# USB2_Replication.net
KiCad netlist of a schematic drawn in Altium Designer
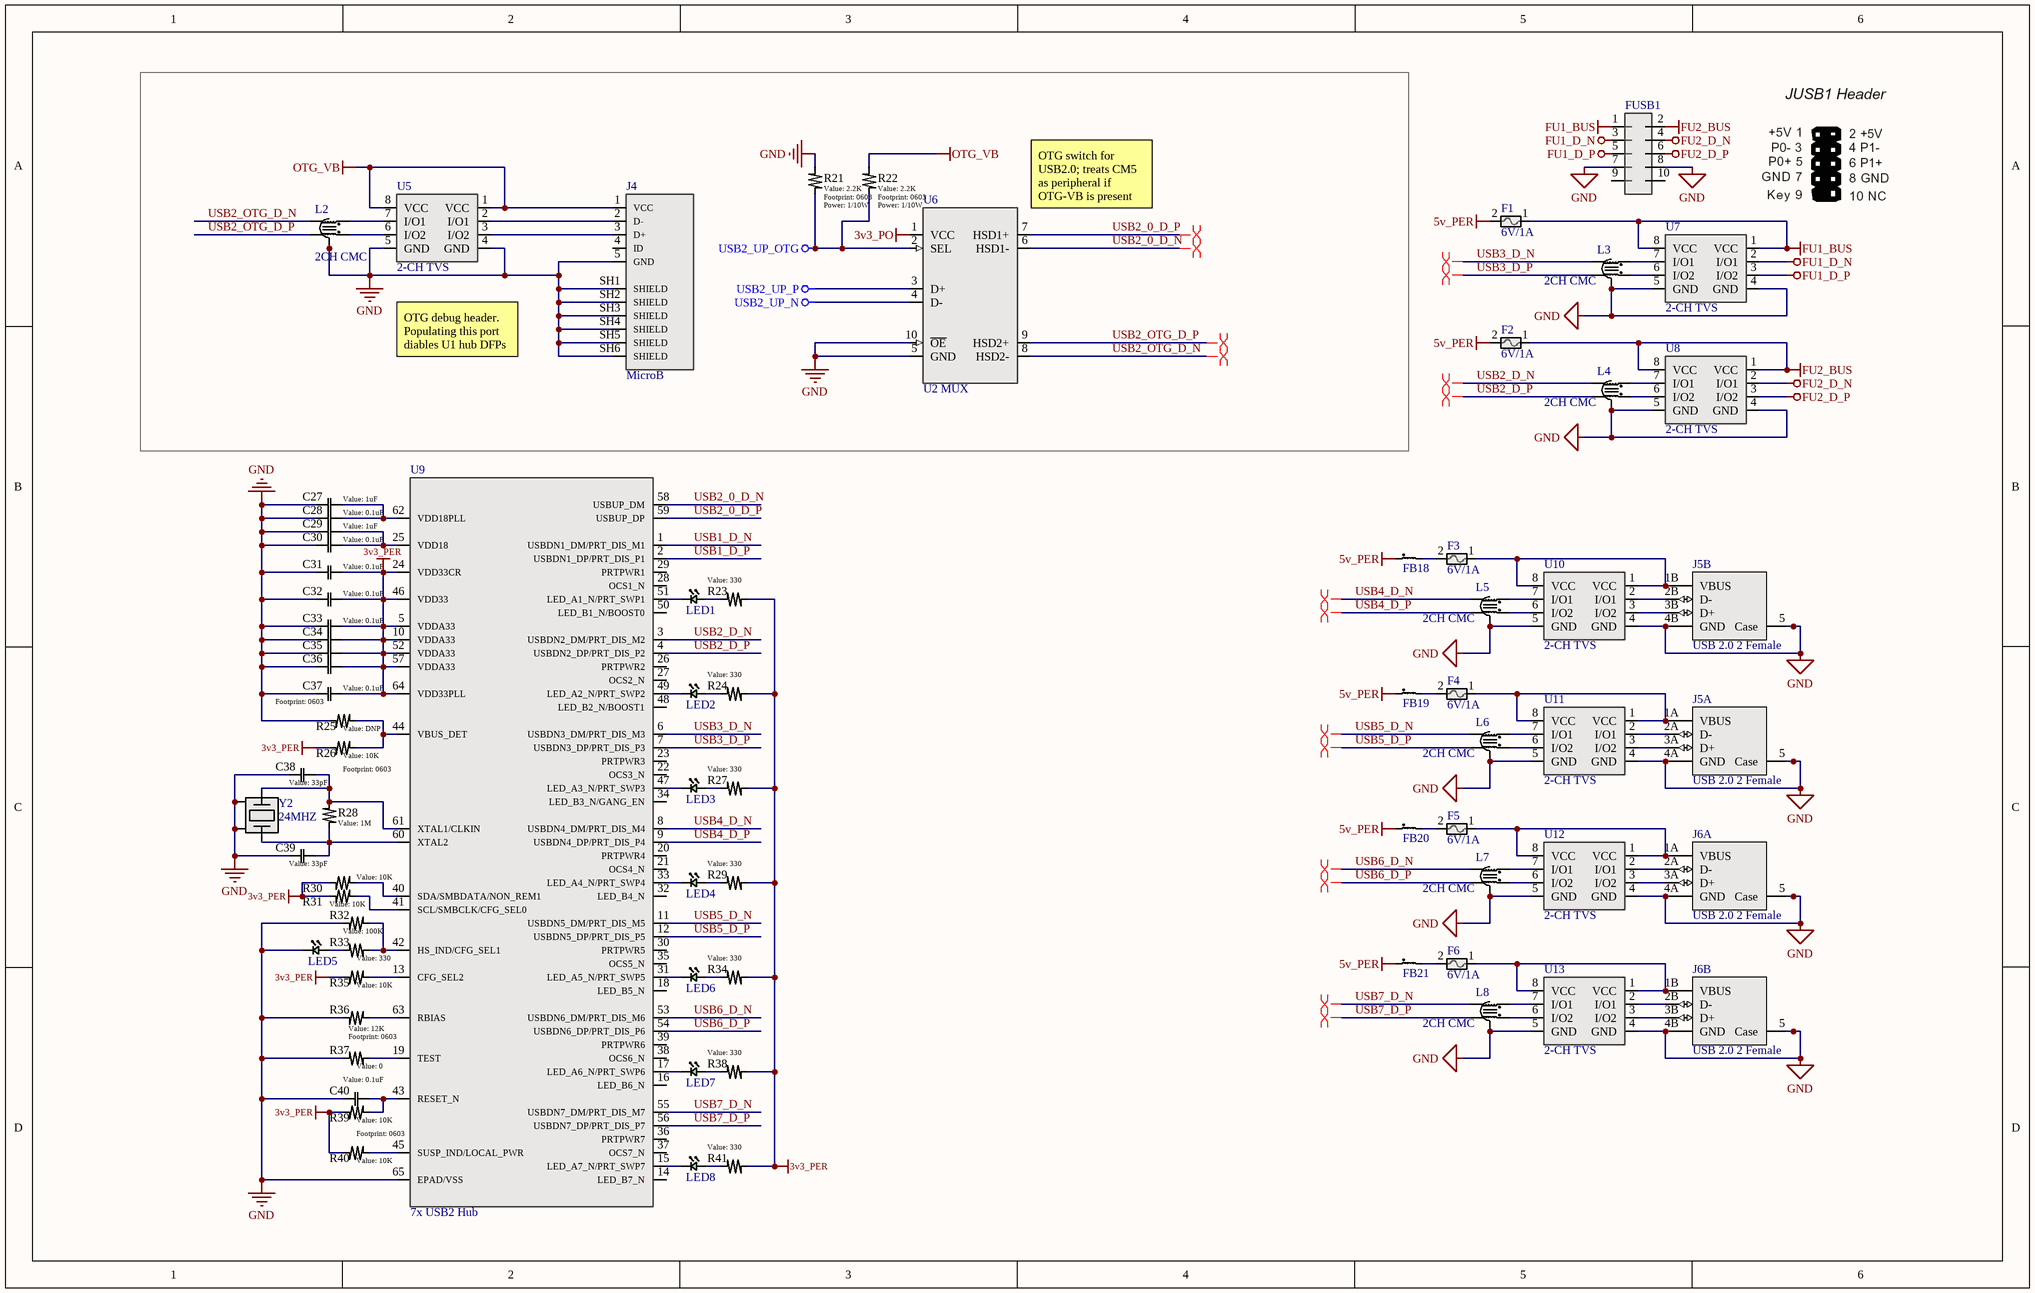
[diagram p0: USB2_Replication.SchDoc]

(export (version "E")
  (design (tool "Eeschema 10.0.6"))
  (components
    (comp (ref "C27")
      (value "1uF")
      (footprint "0603")
      (fields
        (field (name "VOLTAGE") "10V")
        (field (name "TOLERANCE") "10%")
        (field (name "Comment") "Generic Capacitor")
      )
      (libsource (lib "Capacitors") (part "Generic Capacitor"))
    )
    (comp (ref "C28")
      (value "0.1uF")
      (footprint "0603")
      (fields
        (field (name "VOLTAGE") "10V")
        (field (name "TOLERANCE") "10%")
        (field (name "Comment") "Generic Capacitor")
      )
      (libsource (lib "Capacitors") (part "Generic Capacitor"))
    )
    (comp (ref "C29")
      (value "1uF")
      (footprint "0603")
      (fields
        (field (name "VOLTAGE") "10V")
        (field (name "TOLERANCE") "10%")
        (field (name "Comment") "Generic Capacitor")
      )
      (libsource (lib "Capacitors") (part "Generic Capacitor"))
    )
    (comp (ref "C30")
      (value "0.1uF")
      (footprint "0603")
      (fields
        (field (name "VOLTAGE") "10V")
        (field (name "TOLERANCE") "10%")
        (field (name "Comment") "Generic Capacitor")
      )
      (libsource (lib "Capacitors") (part "Generic Capacitor"))
    )
    (comp (ref "C31")
      (value "0.1uF")
      (footprint "0603")
      (fields
        (field (name "VOLTAGE") "10V")
        (field (name "TOLERANCE") "10%")
        (field (name "Comment") "Generic Capacitor")
      )
      (libsource (lib "Capacitors") (part "Generic Capacitor"))
    )
    (comp (ref "C32")
      (value "0.1uF")
      (footprint "0603")
      (fields
        (field (name "VOLTAGE") "10V")
        (field (name "TOLERANCE") "10%")
        (field (name "Comment") "Generic Capacitor")
      )
      (libsource (lib "Capacitors") (part "Generic Capacitor"))
    )
    (comp (ref "C33")
      (value "0.1uF")
      (footprint "0603")
      (fields
        (field (name "VOLTAGE") "10V")
        (field (name "TOLERANCE") "10%")
        (field (name "Comment") "Generic Capacitor")
      )
      (libsource (lib "Capacitors") (part "Generic Capacitor"))
    )
    (comp (ref "C34")
      (value "Generic Capacitor")
      (footprint "0603")
      (fields (field (name "VOLTAGE") "10V") (field (name "TOLERANCE") "10%"))
      (libsource (lib "Capacitors") (part "Generic Capacitor"))
    )
    (comp (ref "C35")
      (value "Generic Capacitor")
      (footprint "0603")
      (fields (field (name "VOLTAGE") "10V") (field (name "TOLERANCE") "10%"))
      (libsource (lib "Capacitors") (part "Generic Capacitor"))
    )
    (comp (ref "C36")
      (value "Generic Capacitor")
      (footprint "0603")
      (fields (field (name "VOLTAGE") "10V") (field (name "TOLERANCE") "10%"))
      (libsource (lib "Capacitors") (part "Generic Capacitor"))
    )
    (comp (ref "C37")
      (value "0.1uF")
      (footprint "0603")
      (fields
        (field (name "VOLTAGE") "10V")
        (field (name "TOLERANCE") "10%")
        (field (name "Comment") "Generic Capacitor")
      )
      (libsource (lib "Capacitors") (part "Generic Capacitor"))
    )
    (comp (ref "C38")
      (value "33pF")
      (footprint "0603")
      (fields
        (field (name "VOLTAGE") "10V")
        (field (name "TOLERANCE") "10%")
        (field (name "Comment") "Generic Capacitor")
      )
      (libsource (lib "Capacitors") (part "Generic Capacitor"))
    )
    (comp (ref "C39")
      (value "33pF")
      (footprint "0603")
      (fields
        (field (name "VOLTAGE") "10V")
        (field (name "TOLERANCE") "10%")
        (field (name "Comment") "Generic Capacitor")
      )
      (libsource (lib "Capacitors") (part "Generic Capacitor"))
    )
    (comp (ref "C40")
      (value "0.1uF")
      (footprint "0603")
      (fields
        (field (name "VOLTAGE") "10V")
        (field (name "TOLERANCE") "10%")
        (field (name "Comment") "Generic Capacitor")
      )
      (libsource (lib "Capacitors") (part "Generic Capacitor"))
    )
    (comp (ref "F1")
      (value "6V/1A")
      (footprint "0805")
      (description "Polymeric PTC Resettable Fuse 6V 1 A Ih Surface Mount 0805 (2012 Metric), Concave")
      (fields (field (name "MANUFACTURER") "Bel") (field (name "MANUFACTURER PART NUMBER") "0ZCK0100FF2E"))
      (libsource (lib "Regulators") (part "0ZCK0100FF2E"))
    )
    (comp (ref "F2")
      (value "6V/1A")
      (footprint "0805")
      (description "Polymeric PTC Resettable Fuse 6V 1 A Ih Surface Mount 0805 (2012 Metric), Concave")
      (fields (field (name "MANUFACTURER") "Bel") (field (name "MANUFACTURER PART NUMBER") "0ZCK0100FF2E"))
      (libsource (lib "Regulators") (part "0ZCK0100FF2E"))
    )
    (comp (ref "F3")
      (value "6V/1A")
      (footprint "0805")
      (description "Polymeric PTC Resettable Fuse 6V 1 A Ih Surface Mount 0805 (2012 Metric), Concave")
      (fields (field (name "MANUFACTURER") "Bel") (field (name "MANUFACTURER PART NUMBER") "0ZCK0100FF2E"))
      (libsource (lib "Regulators") (part "0ZCK0100FF2E"))
    )
    (comp (ref "F4")
      (value "6V/1A")
      (footprint "0805")
      (description "Polymeric PTC Resettable Fuse 6V 1 A Ih Surface Mount 0805 (2012 Metric), Concave")
      (fields (field (name "MANUFACTURER") "Bel") (field (name "MANUFACTURER PART NUMBER") "0ZCK0100FF2E"))
      (libsource (lib "Regulators") (part "0ZCK0100FF2E"))
    )
    (comp (ref "F5")
      (value "6V/1A")
      (footprint "0805")
      (description "Polymeric PTC Resettable Fuse 6V 1 A Ih Surface Mount 0805 (2012 Metric), Concave")
      (fields (field (name "MANUFACTURER") "Bel") (field (name "MANUFACTURER PART NUMBER") "0ZCK0100FF2E"))
      (libsource (lib "Regulators") (part "0ZCK0100FF2E"))
    )
    (comp (ref "F6")
      (value "6V/1A")
      (footprint "0805")
      (description "Polymeric PTC Resettable Fuse 6V 1 A Ih Surface Mount 0805 (2012 Metric), Concave")
      (fields (field (name "MANUFACTURER") "Bel") (field (name "MANUFACTURER PART NUMBER") "0ZCK0100FF2E"))
      (libsource (lib "Regulators") (part "0ZCK0100FF2E"))
    )
    (comp (ref "FB18")
      (value "0603 Ferrite")
      (footprint "0603")
      (description "120 Ohms @ 100 MHz 1 Signal Line Ferrite Bead 0603 (1608 Metric) 500mA 180mOhm")
      (fields
        (field (name "MANUFACTURER") "Pulse")
        (field (name "MANUFACTURER PART NUMBER") "PE-0603FB121ST")
      )
      (libsource (lib "Inductors") (part "PE-0603FB121ST"))
    )
    (comp (ref "FB19")
      (value "0603 Ferrite")
      (footprint "0603")
      (description "120 Ohms @ 100 MHz 1 Signal Line Ferrite Bead 0603 (1608 Metric) 500mA 180mOhm")
      (fields
        (field (name "MANUFACTURER") "Pulse")
        (field (name "MANUFACTURER PART NUMBER") "PE-0603FB121ST")
      )
      (libsource (lib "Inductors") (part "PE-0603FB121ST"))
    )
    (comp (ref "FB20")
      (value "0603 Ferrite")
      (footprint "0603")
      (description "120 Ohms @ 100 MHz 1 Signal Line Ferrite Bead 0603 (1608 Metric) 500mA 180mOhm")
      (fields
        (field (name "MANUFACTURER") "Pulse")
        (field (name "MANUFACTURER PART NUMBER") "PE-0603FB121ST")
      )
      (libsource (lib "Inductors") (part "PE-0603FB121ST"))
    )
    (comp (ref "FB21")
      (value "0603 Ferrite")
      (footprint "0603")
      (description "120 Ohms @ 100 MHz 1 Signal Line Ferrite Bead 0603 (1608 Metric) 500mA 180mOhm")
      (fields
        (field (name "MANUFACTURER") "Pulse")
        (field (name "MANUFACTURER PART NUMBER") "PE-0603FB121ST")
      )
      (libsource (lib "Inductors") (part "PE-0603FB121ST"))
    )
    (comp (ref "FUSB1")
      (value "10pinMobo")
      (footprint "10pinMobo")
      (description "10pin motherboard jack")
      (libsource (lib "Connectors") (part "10pinMobo"))
    )
    (comp (ref "J4")
      (value "MicroB")
      (footprint "10118194-0001LF")
      (description "Micro USB, Input Output Connectors, B TYPE RECEPTACLE with flange")
      (fields (field (name "MF") "Amphenol ICC") (field (name "MP") "10118194-0001LF"))
      (libsource (lib "Connectors") (part "10118194-0001LF"))
    )
    (comp (ref "J5")
      (value "USB 2.0 2 Female")
      (footprint "907-111A1022D10200")
      (description "USB 2.0 2 8 Female Type-A Plugin USB Connectors ROHS")
      (libsource (lib "Connectors") (part "907-111A1022D10200"))
    )
    (comp (ref "J6")
      (value "USB 2.0 2 Female")
      (footprint "907-111A1022D10200")
      (description "USB 2.0 2 8 Female Type-A Plugin USB Connectors ROHS")
      (libsource (lib "Connectors") (part "907-111A1022D10200"))
    )
    (comp (ref "L2")
      (value "2CH CMC")
      (footprint "SMD-6-2CH")
      (description "35Ω@100MHz -40℃~+85℃ 4Ω 5V 2 100mA SMD Common Mode Filters ROHS")
      (libsource (lib "Inductors") (part "ICMEF112P350MFR"))
    )
    (comp (ref "L3")
      (value "2CH CMC")
      (footprint "SMD-6-2CH")
      (description "35Ω@100MHz -40℃~+85℃ 4Ω 5V 2 100mA SMD Common Mode Filters ROHS")
      (libsource (lib "Inductors") (part "ICMEF112P350MFR"))
    )
    (comp (ref "L4")
      (value "2CH CMC")
      (footprint "SMD-6-2CH")
      (description "35Ω@100MHz -40℃~+85℃ 4Ω 5V 2 100mA SMD Common Mode Filters ROHS")
      (libsource (lib "Inductors") (part "ICMEF112P350MFR"))
    )
    (comp (ref "L5")
      (value "2CH CMC")
      (footprint "SMD-6-2CH")
      (description "35Ω@100MHz -40℃~+85℃ 4Ω 5V 2 100mA SMD Common Mode Filters ROHS")
      (libsource (lib "Inductors") (part "ICMEF112P350MFR"))
    )
    (comp (ref "L6")
      (value "2CH CMC")
      (footprint "SMD-6-2CH")
      (description "35Ω@100MHz -40℃~+85℃ 4Ω 5V 2 100mA SMD Common Mode Filters ROHS")
      (libsource (lib "Inductors") (part "ICMEF112P350MFR"))
    )
    (comp (ref "L7")
      (value "2CH CMC")
      (footprint "SMD-6-2CH")
      (description "35Ω@100MHz -40℃~+85℃ 4Ω 5V 2 100mA SMD Common Mode Filters ROHS")
      (libsource (lib "Inductors") (part "ICMEF112P350MFR"))
    )
    (comp (ref "L8")
      (value "2CH CMC")
      (footprint "SMD-6-2CH")
      (description "35Ω@100MHz -40℃~+85℃ 4Ω 5V 2 100mA SMD Common Mode Filters ROHS")
      (libsource (lib "Inductors") (part "ICMEF112P350MFR"))
    )
    (comp (ref "LED1")
      (value "LTST-C191KGKT")
      (footprint "0603 (1608 Metric) Concave")
      (description "LED Uni-Color Green 574nm 2-Pin Chip LED T/R")
      (libsource (lib "Gamber - Johnson LLC") (part "LTST-C191KGKT"))
    )
    (comp (ref "LED2")
      (value "LTST-C191KGKT")
      (footprint "0603 (1608 Metric) Concave")
      (description "LED Uni-Color Green 574nm 2-Pin Chip LED T/R")
      (libsource (lib "Gamber - Johnson LLC") (part "LTST-C191KGKT"))
    )
    (comp (ref "LED3")
      (value "LTST-C191KGKT")
      (footprint "0603 (1608 Metric) Concave")
      (description "LED Uni-Color Green 574nm 2-Pin Chip LED T/R")
      (libsource (lib "Gamber - Johnson LLC") (part "LTST-C191KGKT"))
    )
    (comp (ref "LED4")
      (value "LTST-C191KGKT")
      (footprint "0603 (1608 Metric) Concave")
      (description "LED Uni-Color Green 574nm 2-Pin Chip LED T/R")
      (libsource (lib "Gamber - Johnson LLC") (part "LTST-C191KGKT"))
    )
    (comp (ref "LED5")
      (value "LTST-C191KGKT")
      (footprint "0603 (1608 Metric) Concave")
      (description "LED Uni-Color Green 574nm 2-Pin Chip LED T/R")
      (libsource (lib "Gamber - Johnson LLC") (part "LTST-C191KGKT"))
    )
    (comp (ref "LED6")
      (value "LTST-C191KGKT")
      (footprint "0603 (1608 Metric) Concave")
      (description "LED Uni-Color Green 574nm 2-Pin Chip LED T/R")
      (libsource (lib "Gamber - Johnson LLC") (part "LTST-C191KGKT"))
    )
    (comp (ref "LED7")
      (value "LTST-C191KGKT")
      (footprint "0603 (1608 Metric) Concave")
      (description "LED Uni-Color Green 574nm 2-Pin Chip LED T/R")
      (libsource (lib "Gamber - Johnson LLC") (part "LTST-C191KGKT"))
    )
    (comp (ref "LED8")
      (value "LTST-C191KGKT")
      (footprint "0603 (1608 Metric) Concave")
      (description "LED Uni-Color Green 574nm 2-Pin Chip LED T/R")
      (libsource (lib "Gamber - Johnson LLC") (part "LTST-C191KGKT"))
    )
    (comp (ref "R21")
      (value "2.2K")
      (footprint "0603")
      (fields
        (field (name "TOLERANCE") "1%")
        (field (name "POWER") "1/10W")
        (field (name "Comment") "Generic Resistor")
      )
      (libsource (lib "Resistors") (part "Generic Resistor"))
    )
    (comp (ref "R22")
      (value "2.2K")
      (footprint "0603")
      (fields
        (field (name "TOLERANCE") "1%")
        (field (name "POWER") "1/10W")
        (field (name "Comment") "Generic Resistor")
      )
      (libsource (lib "Resistors") (part "Generic Resistor"))
    )
    (comp (ref "R23")
      (value "330")
      (footprint "0603")
      (fields
        (field (name "TOLERANCE") "1%")
        (field (name "POWER") "1/10W")
        (field (name "Comment") "Generic Resistor")
      )
      (libsource (lib "Resistors") (part "Generic Resistor"))
    )
    (comp (ref "R24")
      (value "330")
      (footprint "0603")
      (fields
        (field (name "TOLERANCE") "1%")
        (field (name "POWER") "1/10W")
        (field (name "Comment") "Generic Resistor")
      )
      (libsource (lib "Resistors") (part "Generic Resistor"))
    )
    (comp (ref "R25")
      (value "DNP")
      (footprint "0603")
      (fields
        (field (name "TOLERANCE") "1%")
        (field (name "POWER") "1/10W")
        (field (name "Comment") "Generic Resistor")
      )
      (libsource (lib "Resistors") (part "Generic Resistor"))
    )
    (comp (ref "R26")
      (value "10K")
      (footprint "0603")
      (fields
        (field (name "TOLERANCE") "1%")
        (field (name "POWER") "1/10W")
        (field (name "Comment") "Generic Resistor")
      )
      (libsource (lib "Resistors") (part "Generic Resistor"))
    )
    (comp (ref "R27")
      (value "330")
      (footprint "0603")
      (fields
        (field (name "TOLERANCE") "1%")
        (field (name "POWER") "1/10W")
        (field (name "Comment") "Generic Resistor")
      )
      (libsource (lib "Resistors") (part "Generic Resistor"))
    )
    (comp (ref "R28")
      (value "1M")
      (footprint "0603")
      (fields
        (field (name "TOLERANCE") "1%")
        (field (name "POWER") "1/10W")
        (field (name "Comment") "Generic Resistor")
      )
      (libsource (lib "Resistors") (part "Generic Resistor"))
    )
    (comp (ref "R29")
      (value "330")
      (footprint "0603")
      (fields
        (field (name "TOLERANCE") "1%")
        (field (name "POWER") "1/10W")
        (field (name "Comment") "Generic Resistor")
      )
      (libsource (lib "Resistors") (part "Generic Resistor"))
    )
    (comp (ref "R30")
      (value "10K")
      (footprint "0603")
      (fields
        (field (name "TOLERANCE") "1%")
        (field (name "POWER") "1/10W")
        (field (name "Comment") "Generic Resistor")
      )
      (libsource (lib "Resistors") (part "Generic Resistor"))
    )
    (comp (ref "R31")
      (value "10K")
      (footprint "0603")
      (fields
        (field (name "TOLERANCE") "1%")
        (field (name "POWER") "1/10W")
        (field (name "Comment") "Generic Resistor")
      )
      (libsource (lib "Resistors") (part "Generic Resistor"))
    )
    (comp (ref "R32")
      (value "100K")
      (footprint "0603")
      (fields
        (field (name "TOLERANCE") "1%")
        (field (name "POWER") "1/10W")
        (field (name "Comment") "Generic Resistor")
      )
      (libsource (lib "Resistors") (part "Generic Resistor"))
    )
    (comp (ref "R33")
      (value "330")
      (footprint "0603")
      (fields
        (field (name "TOLERANCE") "1%")
        (field (name "POWER") "1/10W")
        (field (name "Comment") "Generic Resistor")
      )
      (libsource (lib "Resistors") (part "Generic Resistor"))
    )
    (comp (ref "R34")
      (value "330")
      (footprint "0603")
      (fields
        (field (name "TOLERANCE") "1%")
        (field (name "POWER") "1/10W")
        (field (name "Comment") "Generic Resistor")
      )
      (libsource (lib "Resistors") (part "Generic Resistor"))
    )
    (comp (ref "R35")
      (value "10K")
      (footprint "0603")
      (fields
        (field (name "TOLERANCE") "1%")
        (field (name "POWER") "1/10W")
        (field (name "Comment") "Generic Resistor")
      )
      (libsource (lib "Resistors") (part "Generic Resistor"))
    )
    (comp (ref "R36")
      (value "12K")
      (footprint "0603")
      (fields
        (field (name "TOLERANCE") "1%")
        (field (name "POWER") "1/10W")
        (field (name "Comment") "Generic Resistor")
      )
      (libsource (lib "Resistors") (part "Generic Resistor"))
    )
    (comp (ref "R37")
      (value "0")
      (footprint "0603")
      (fields
        (field (name "TOLERANCE") "1%")
        (field (name "POWER") "1/10W")
        (field (name "Comment") "Generic Resistor")
      )
      (libsource (lib "Resistors") (part "Generic Resistor"))
    )
    (comp (ref "R38")
      (value "330")
      (footprint "0603")
      (fields
        (field (name "TOLERANCE") "1%")
        (field (name "POWER") "1/10W")
        (field (name "Comment") "Generic Resistor")
      )
      (libsource (lib "Resistors") (part "Generic Resistor"))
    )
    (comp (ref "R39")
      (value "10K")
      (footprint "0603")
      (fields
        (field (name "TOLERANCE") "1%")
        (field (name "POWER") "1/10W")
        (field (name "Comment") "Generic Resistor")
      )
      (libsource (lib "Resistors") (part "Generic Resistor"))
    )
    (comp (ref "R40")
      (value "10K")
      (footprint "0603")
      (fields
        (field (name "TOLERANCE") "1%")
        (field (name "POWER") "1/10W")
        (field (name "Comment") "Generic Resistor")
      )
      (libsource (lib "Resistors") (part "Generic Resistor"))
    )
    (comp (ref "R41")
      (value "330")
      (footprint "0603")
      (fields
        (field (name "TOLERANCE") "1%")
        (field (name "POWER") "1/10W")
        (field (name "Comment") "Generic Resistor")
      )
      (libsource (lib "Resistors") (part "Generic Resistor"))
    )
    (comp (ref "U5")
      (value "2-CH TVS")
      (footprint "8-SOIC")
      (description "TVS DIODE 5.25VWM 8-SOIC")
      (libsource (lib "Diodes") (part "USB6B1RL"))
    )
    (comp (ref "U6")
      (value "U2 MUX")
      (footprint "MSOP-10")
      (description "FSUSB42 Series DPDT 4.3 V 480 Mbps SMT Hi Speed USB 2.0 Switch - MSOP-10")
      (fields (field (name "MF") "ON Semiconductor") (field (name "MP") "FSUSB42MUX"))
      (libsource (lib "Misc ICs") (part "FSUSB42MUX"))
    )
    (comp (ref "U7")
      (value "2-CH TVS")
      (footprint "8-SOIC")
      (description "TVS DIODE 5.25VWM 8-SOIC")
      (libsource (lib "Diodes") (part "USB6B1RL"))
    )
    (comp (ref "U8")
      (value "2-CH TVS")
      (footprint "8-SOIC")
      (description "TVS DIODE 5.25VWM 8-SOIC")
      (libsource (lib "Diodes") (part "USB6B1RL"))
    )
    (comp (ref "U9")
      (value "7x USB2 Hub")
      (footprint "QFN-64")
      (description "USB Hub Controller USB 2.0 USB Interface 64-QFN (9x9)")
      (libsource (lib "Hub ICs") (part "USB2517-JZX"))
    )
    (comp (ref "U10")
      (value "2-CH TVS")
      (footprint "8-SOIC")
      (description "TVS DIODE 5.25VWM 8-SOIC")
      (libsource (lib "Diodes") (part "USB6B1RL"))
    )
    (comp (ref "U11")
      (value "2-CH TVS")
      (footprint "8-SOIC")
      (description "TVS DIODE 5.25VWM 8-SOIC")
      (libsource (lib "Diodes") (part "USB6B1RL"))
    )
    (comp (ref "U12")
      (value "2-CH TVS")
      (footprint "8-SOIC")
      (description "TVS DIODE 5.25VWM 8-SOIC")
      (libsource (lib "Diodes") (part "USB6B1RL"))
    )
    (comp (ref "U13")
      (value "2-CH TVS")
      (footprint "8-SOIC")
      (description "TVS DIODE 5.25VWM 8-SOIC")
      (libsource (lib "Diodes") (part "USB6B1RL"))
    )
    (comp (ref "Y2")
      (value "24MHZ")
      (footprint "SMD2520-4P")
      (description "24MHz 20pF ±10ppm ±30ppm SMD-2520-4P Crystals ROHS")
      (libsource (lib "Clock ICs") (part "CM4024M00020001"))
    )
  )
  (nets
    (net (code "1") (name "/USB1_D_N") (class "Default")
      (node (ref "U9") (pin "1") (pinfunction "USBDN1_DM/PRT_DIS_M1_1") (pintype "bidirectional"))
    )
    (net (code "2") (name "/USB1_D_P") (class "Default")
      (node (ref "U9") (pin "2") (pinfunction "USBDN1_DP/PRT_DIS_P1_2") (pintype "bidirectional"))
    )
    (net (code "3") (name "/USB2_0_D_N") (class "Default")
      (node (ref "U6") (pin "6") (pinfunction "HSD1-_6") (pintype "bidirectional"))
      (node (ref "U9") (pin "58") (pinfunction "USBUP_DM_58") (pintype "bidirectional"))
    )
    (net (code "4") (name "/USB2_0_D_P") (class "Default")
      (node (ref "U6") (pin "7") (pinfunction "HSD1+_7") (pintype "bidirectional"))
      (node (ref "U9") (pin "59") (pinfunction "USBUP_DP_59") (pintype "bidirectional"))
    )
    (net (code "5") (name "/USB2_D_N") (class "Default")
      (node (ref "L4") (pin "4") (pinfunction "4_4") (pintype "passive"))
      (node (ref "U9") (pin "3") (pinfunction "USBDN2_DM/PRT_DIS_M2_3") (pintype "bidirectional"))
    )
    (net (code "6") (name "/USB2_D_P") (class "Default")
      (node (ref "L4") (pin "3") (pinfunction "3_3") (pintype "passive"))
      (node (ref "U9") (pin "4") (pinfunction "USBDN2_DP/PRT_DIS_P2_4") (pintype "bidirectional"))
    )
    (net (code "7") (name "/USB2_OTG_D_N") (class "Default")
      (node (ref "L2") (pin "4") (pinfunction "4_4") (pintype "passive"))
      (node (ref "U6") (pin "8") (pinfunction "HSD2-_8") (pintype "bidirectional"))
    )
    (net (code "8") (name "/USB2_OTG_D_P") (class "Default")
      (node (ref "L2") (pin "3") (pinfunction "3_3") (pintype "passive"))
      (node (ref "U6") (pin "9") (pinfunction "HSD2+_9") (pintype "bidirectional"))
    )
    (net (code "9") (name "/USB3_D_N") (class "Default")
      (node (ref "L3") (pin "4") (pinfunction "4_4") (pintype "passive"))
      (node (ref "U9") (pin "6") (pinfunction "USBDN3_DM/PRT_DIS_M3_6") (pintype "bidirectional"))
    )
    (net (code "10") (name "/USB3_D_P") (class "Default")
      (node (ref "L3") (pin "3") (pinfunction "3_3") (pintype "passive"))
      (node (ref "U9") (pin "7") (pinfunction "USBDN3_DP/PRT_DIS_P3_7") (pintype "bidirectional"))
    )
    (net (code "11") (name "/USB4_D_N") (class "Default")
      (node (ref "L5") (pin "4") (pinfunction "4_4") (pintype "passive"))
      (node (ref "U9") (pin "8") (pinfunction "USBDN4_DM/PRT_DIS_M4_8") (pintype "bidirectional"))
    )
    (net (code "12") (name "/USB4_D_P") (class "Default")
      (node (ref "L5") (pin "3") (pinfunction "3_3") (pintype "passive"))
      (node (ref "U9") (pin "9") (pinfunction "USBDN4_DP/PRT_DIS_P4_9") (pintype "bidirectional"))
    )
    (net (code "13") (name "/USB5_D_N") (class "Default")
      (node (ref "L6") (pin "4") (pinfunction "4_4") (pintype "passive"))
      (node (ref "U9") (pin "11") (pinfunction "USBDN5_DM/PRT_DIS_M5_11") (pintype "bidirectional"))
    )
    (net (code "14") (name "/USB5_D_P") (class "Default")
      (node (ref "L6") (pin "3") (pinfunction "3_3") (pintype "passive"))
      (node (ref "U9") (pin "12") (pinfunction "USBDN5_DP/PRT_DIS_P5_12") (pintype "bidirectional"))
    )
    (net (code "15") (name "/USB6_D_N") (class "Default")
      (node (ref "L7") (pin "4") (pinfunction "4_4") (pintype "passive"))
      (node (ref "U9") (pin "53") (pinfunction "USBDN6_DM/PRT_DIS_M6_53") (pintype "bidirectional"))
    )
    (net (code "16") (name "/USB6_D_P") (class "Default")
      (node (ref "L7") (pin "3") (pinfunction "3_3") (pintype "passive"))
      (node (ref "U9") (pin "54") (pinfunction "USBDN6_DP/PRT_DIS_P6_54") (pintype "bidirectional"))
    )
    (net (code "17") (name "/USB7_D_N") (class "Default")
      (node (ref "L8") (pin "4") (pinfunction "4_4") (pintype "passive"))
      (node (ref "U9") (pin "55") (pinfunction "USBDN7_DM/PRT_DIS_M7_55") (pintype "bidirectional"))
    )
    (net (code "18") (name "/USB7_D_P") (class "Default")
      (node (ref "L8") (pin "3") (pinfunction "3_3") (pintype "passive"))
      (node (ref "U9") (pin "56") (pinfunction "USBDN7_DP/PRT_DIS_P7_56") (pintype "bidirectional"))
    )
    (net (code "19") (name "3v3_PER") (class "Default")
      (node (ref "C31") (pin "1") (pinfunction "1_1") (pintype "passive"))
      (node (ref "C32") (pin "1") (pinfunction "1_1") (pintype "passive"))
      (node (ref "C33") (pin "1") (pinfunction "1_1") (pintype "passive"))
      (node (ref "C34") (pin "1") (pinfunction "1_1") (pintype "passive"))
      (node (ref "C35") (pin "1") (pinfunction "1_1") (pintype "passive"))
      (node (ref "C36") (pin "1") (pinfunction "1_1") (pintype "passive"))
      (node (ref "C37") (pin "1") (pinfunction "1_1") (pintype "passive"))
      (node (ref "R23") (pin "2") (pinfunction "2_2") (pintype "passive"))
      (node (ref "R24") (pin "2") (pinfunction "2_2") (pintype "passive"))
      (node (ref "R26") (pin "1") (pinfunction "1_1") (pintype "passive"))
      (node (ref "R27") (pin "2") (pinfunction "2_2") (pintype "passive"))
      (node (ref "R29") (pin "2") (pinfunction "2_2") (pintype "passive"))
      (node (ref "R30") (pin "1") (pinfunction "1_1") (pintype "passive"))
      (node (ref "R31") (pin "1") (pinfunction "1_1") (pintype "passive"))
      (node (ref "R34") (pin "2") (pinfunction "2_2") (pintype "passive"))
      (node (ref "R35") (pin "1") (pinfunction "1_1") (pintype "passive"))
      (node (ref "R38") (pin "2") (pinfunction "2_2") (pintype "passive"))
      (node (ref "R39") (pin "1") (pinfunction "1_1") (pintype "passive"))
      (node (ref "R40") (pin "1") (pinfunction "1_1") (pintype "passive"))
      (node (ref "R41") (pin "2") (pinfunction "2_2") (pintype "passive"))
      (node (ref "U9") (pin "10") (pinfunction "VDDA33_10") (pintype "power_in"))
      (node (ref "U9") (pin "24") (pinfunction "VDD33CR_24") (pintype "power_in"))
      (node (ref "U9") (pin "46") (pinfunction "VDD33_46") (pintype "power_in"))
      (node (ref "U9") (pin "5") (pinfunction "VDDA33_5") (pintype "power_in"))
      (node (ref "U9") (pin "52") (pinfunction "VDDA33_52") (pintype "power_in"))
      (node (ref "U9") (pin "57") (pinfunction "VDDA33_57") (pintype "power_in"))
      (node (ref "U9") (pin "64") (pinfunction "VDD33PLL_64") (pintype "power_in"))
    )
    (net (code "20") (name "3v3_PO") (class "Default")
      (node (ref "U6") (pin "1") (pinfunction "VCC_1") (pintype "power_in"))
    )
    (net (code "21") (name "5v_PER") (class "Default")
      (node (ref "F1") (pin "2") (pinfunction "2_2") (pintype "passive"))
      (node (ref "F2") (pin "2") (pinfunction "2_2") (pintype "passive"))
      (node (ref "FB18") (pin "1") (pinfunction "1_1") (pintype "passive"))
      (node (ref "FB19") (pin "1") (pinfunction "1_1") (pintype "passive"))
      (node (ref "FB20") (pin "1") (pinfunction "1_1") (pintype "passive"))
      (node (ref "FB21") (pin "1") (pinfunction "1_1") (pintype "passive"))
    )
    (net (code "22") (name "FU1_BUS") (class "Default")
      (node (ref "F1") (pin "1") (pinfunction "1_1") (pintype "passive"))
      (node (ref "FUSB1") (pin "1") (pinfunction "1_1") (pintype "passive"))
      (node (ref "U7") (pin "1") (pinfunction "VCC_1") (pintype "power_in"))
      (node (ref "U7") (pin "8") (pinfunction "VCC_8") (pintype "power_in"))
    )
    (net (code "23") (name "FU1_D_N") (class "Default")
      (node (ref "FUSB1") (pin "3") (pinfunction "3_3") (pintype "passive"))
      (node (ref "U7") (pin "2") (pinfunction "I/O1_2") (pintype "bidirectional"))
    )
    (net (code "24") (name "FU1_D_P") (class "Default")
      (node (ref "FUSB1") (pin "5") (pinfunction "5_5") (pintype "passive"))
      (node (ref "U7") (pin "3") (pinfunction "I/O2_3") (pintype "bidirectional"))
    )
    (net (code "25") (name "FU2_BUS") (class "Default")
      (node (ref "F2") (pin "1") (pinfunction "1_1") (pintype "passive"))
      (node (ref "FUSB1") (pin "2") (pinfunction "2_2") (pintype "passive"))
      (node (ref "U8") (pin "1") (pinfunction "VCC_1") (pintype "power_in"))
      (node (ref "U8") (pin "8") (pinfunction "VCC_8") (pintype "power_in"))
    )
    (net (code "26") (name "FU2_D_N") (class "Default")
      (node (ref "FUSB1") (pin "4") (pinfunction "4_4") (pintype "passive"))
      (node (ref "U8") (pin "2") (pinfunction "I/O1_2") (pintype "bidirectional"))
    )
    (net (code "27") (name "FU2_D_P") (class "Default")
      (node (ref "FUSB1") (pin "6") (pinfunction "6_6") (pintype "passive"))
      (node (ref "U8") (pin "3") (pinfunction "I/O2_3") (pintype "bidirectional"))
    )
    (net (code "28") (name "GND") (class "Default")
      (node (ref "C27") (pin "2") (pinfunction "2_2") (pintype "passive"))
      (node (ref "C28") (pin "2") (pinfunction "2_2") (pintype "passive"))
      (node (ref "C29") (pin "2") (pinfunction "2_2") (pintype "passive"))
      (node (ref "C30") (pin "2") (pinfunction "2_2") (pintype "passive"))
      (node (ref "C31") (pin "2") (pinfunction "2_2") (pintype "passive"))
      (node (ref "C32") (pin "2") (pinfunction "2_2") (pintype "passive"))
      (node (ref "C33") (pin "2") (pinfunction "2_2") (pintype "passive"))
      (node (ref "C34") (pin "2") (pinfunction "2_2") (pintype "passive"))
      (node (ref "C35") (pin "2") (pinfunction "2_2") (pintype "passive"))
      (node (ref "C36") (pin "2") (pinfunction "2_2") (pintype "passive"))
      (node (ref "C37") (pin "2") (pinfunction "2_2") (pintype "passive"))
      (node (ref "C38") (pin "2") (pinfunction "2_2") (pintype "passive"))
      (node (ref "C39") (pin "2") (pinfunction "2_2") (pintype "passive"))
      (node (ref "C40") (pin "2") (pinfunction "2_2") (pintype "passive"))
      (node (ref "FUSB1") (pin "7") (pinfunction "7_7") (pintype "passive"))
      (node (ref "FUSB1") (pin "8") (pinfunction "8_8") (pintype "passive"))
      (node (ref "J4") (pin "5") (pinfunction "GND_5") (pintype "power_in"))
      (node (ref "J4") (pin "SH1") (pinfunction "SHIELD_SH1") (pintype "passive"))
      (node (ref "J4") (pin "SH2") (pinfunction "SHIELD_SH2") (pintype "passive"))
      (node (ref "J4") (pin "SH3") (pinfunction "SHIELD_SH3") (pintype "passive"))
      (node (ref "J4") (pin "SH4") (pinfunction "SHIELD_SH4") (pintype "passive"))
      (node (ref "J4") (pin "SH5") (pinfunction "SHIELD_SH5") (pintype "passive"))
      (node (ref "J4") (pin "SH6") (pinfunction "SHIELD_SH6") (pintype "passive"))
      (node (ref "J5") (pin "4A") (pinfunction "GND_4A") (pintype "power_in"))
      (node (ref "J5") (pin "4B") (pinfunction "GND_4B") (pintype "power_in"))
      (node (ref "J5") (pin "5") (pinfunction "Case_5") (pintype "passive"))
      (node (ref "J6") (pin "4A") (pinfunction "GND_4A") (pintype "power_in"))
      (node (ref "J6") (pin "4B") (pinfunction "GND_4B") (pintype "power_in"))
      (node (ref "J6") (pin "5") (pinfunction "Case_5") (pintype "passive"))
      (node (ref "L2") (pin "5") (pinfunction "5_5") (pintype "passive"))
      (node (ref "L2") (pin "6") (pinfunction "6_6") (pintype "passive"))
      (node (ref "L3") (pin "5") (pinfunction "5_5") (pintype "passive"))
      (node (ref "L3") (pin "6") (pinfunction "6_6") (pintype "passive"))
      (node (ref "L4") (pin "5") (pinfunction "5_5") (pintype "passive"))
      (node (ref "L4") (pin "6") (pinfunction "6_6") (pintype "passive"))
      (node (ref "L5") (pin "5") (pinfunction "5_5") (pintype "passive"))
      (node (ref "L5") (pin "6") (pinfunction "6_6") (pintype "passive"))
      (node (ref "L6") (pin "5") (pinfunction "5_5") (pintype "passive"))
      (node (ref "L6") (pin "6") (pinfunction "6_6") (pintype "passive"))
      (node (ref "L7") (pin "5") (pinfunction "5_5") (pintype "passive"))
      (node (ref "L7") (pin "6") (pinfunction "6_6") (pintype "passive"))
      (node (ref "L8") (pin "5") (pinfunction "5_5") (pintype "passive"))
      (node (ref "L8") (pin "6") (pinfunction "6_6") (pintype "passive"))
      (node (ref "LED5") (pin "1") (pinfunction "Cathode_1") (pintype "passive"))
      (node (ref "R21") (pin "1") (pinfunction "1_1") (pintype "passive"))
      (node (ref "R25") (pin "1") (pinfunction "1_1") (pintype "passive"))
      (node (ref "R32") (pin "1") (pinfunction "1_1") (pintype "passive"))
      (node (ref "R36") (pin "1") (pinfunction "1_1") (pintype "passive"))
      (node (ref "R37") (pin "1") (pinfunction "1_1") (pintype "passive"))
      (node (ref "U10") (pin "4") (pinfunction "GND_4") (pintype "power_in"))
      (node (ref "U10") (pin "5") (pinfunction "GND_5") (pintype "power_in"))
      (node (ref "U11") (pin "4") (pinfunction "GND_4") (pintype "power_in"))
      (node (ref "U11") (pin "5") (pinfunction "GND_5") (pintype "power_in"))
      (node (ref "U12") (pin "4") (pinfunction "GND_4") (pintype "power_in"))
      (node (ref "U12") (pin "5") (pinfunction "GND_5") (pintype "power_in"))
      (node (ref "U13") (pin "4") (pinfunction "GND_4") (pintype "power_in"))
      (node (ref "U13") (pin "5") (pinfunction "GND_5") (pintype "power_in"))
      (node (ref "U5") (pin "4") (pinfunction "GND_4") (pintype "power_in"))
      (node (ref "U5") (pin "5") (pinfunction "GND_5") (pintype "power_in"))
      (node (ref "U6") (pin "10") (pinfunction "~{OE}_10") (pintype "input"))
      (node (ref "U6") (pin "5") (pinfunction "GND_5") (pintype "power_in"))
      (node (ref "U7") (pin "4") (pinfunction "GND_4") (pintype "power_in"))
      (node (ref "U7") (pin "5") (pinfunction "GND_5") (pintype "power_in"))
      (node (ref "U8") (pin "4") (pinfunction "GND_4") (pintype "power_in"))
      (node (ref "U8") (pin "5") (pinfunction "GND_5") (pintype "power_in"))
      (node (ref "U9") (pin "65") (pinfunction "EPAD/VSS_65") (pintype "passive"))
      (node (ref "Y2") (pin "2") (pinfunction "GND_2") (pintype "power_in"))
      (node (ref "Y2") (pin "4") (pinfunction "GND_4") (pintype "power_in"))
    )
    (net (code "29") (name "Net-(F3-Pad2)") (class "Default")
      (node (ref "F3") (pin "2") (pinfunction "2_2") (pintype "passive"))
      (node (ref "FB18") (pin "2") (pinfunction "2_2") (pintype "passive"))
    )
    (net (code "30") (name "Net-(F4-Pad2)") (class "Default")
      (node (ref "F4") (pin "2") (pinfunction "2_2") (pintype "passive"))
      (node (ref "FB19") (pin "2") (pinfunction "2_2") (pintype "passive"))
    )
    (net (code "31") (name "Net-(F5-Pad2)") (class "Default")
      (node (ref "F5") (pin "2") (pinfunction "2_2") (pintype "passive"))
      (node (ref "FB20") (pin "2") (pinfunction "2_2") (pintype "passive"))
    )
    (net (code "32") (name "Net-(F6-Pad2)") (class "Default")
      (node (ref "F6") (pin "2") (pinfunction "2_2") (pintype "passive"))
      (node (ref "FB21") (pin "2") (pinfunction "2_2") (pintype "passive"))
    )
    (net (code "33") (name "Net-(J4-D+)") (class "Default")
      (node (ref "J4") (pin "3") (pinfunction "D+_3") (pintype "bidirectional"))
      (node (ref "U5") (pin "3") (pinfunction "I/O2_3") (pintype "bidirectional"))
    )
    (net (code "34") (name "Net-(J4-D-)") (class "Default")
      (node (ref "J4") (pin "2") (pinfunction "D-_2") (pintype "bidirectional"))
      (node (ref "U5") (pin "2") (pinfunction "I/O1_2") (pintype "bidirectional"))
    )
    (net (code "35") (name "Net-(J5A-D+)") (class "Default")
      (node (ref "J5") (pin "3A") (pinfunction "D+_3A") (pintype "bidirectional"))
      (node (ref "U11") (pin "3") (pinfunction "I/O2_3") (pintype "bidirectional"))
    )
    (net (code "36") (name "Net-(J5A-D-)") (class "Default")
      (node (ref "J5") (pin "2A") (pinfunction "D-_2A") (pintype "bidirectional"))
      (node (ref "U11") (pin "2") (pinfunction "I/O1_2") (pintype "bidirectional"))
    )
    (net (code "37") (name "Net-(J5A-VBUS)") (class "Default")
      (node (ref "F4") (pin "1") (pinfunction "1_1") (pintype "passive"))
      (node (ref "J5") (pin "1A") (pinfunction "VBUS_1A") (pintype "power_in"))
      (node (ref "U11") (pin "1") (pinfunction "VCC_1") (pintype "power_in"))
      (node (ref "U11") (pin "8") (pinfunction "VCC_8") (pintype "power_in"))
    )
    (net (code "38") (name "Net-(J5B-D+)") (class "Default")
      (node (ref "J5") (pin "3B") (pinfunction "D+_3B") (pintype "bidirectional"))
      (node (ref "U10") (pin "3") (pinfunction "I/O2_3") (pintype "bidirectional"))
    )
    (net (code "39") (name "Net-(J5B-D-)") (class "Default")
      (node (ref "J5") (pin "2B") (pinfunction "D-_2B") (pintype "bidirectional"))
      (node (ref "U10") (pin "2") (pinfunction "I/O1_2") (pintype "bidirectional"))
    )
    (net (code "40") (name "Net-(J5B-VBUS)") (class "Default")
      (node (ref "F3") (pin "1") (pinfunction "1_1") (pintype "passive"))
      (node (ref "J5") (pin "1B") (pinfunction "VBUS_1B") (pintype "power_in"))
      (node (ref "U10") (pin "1") (pinfunction "VCC_1") (pintype "power_in"))
      (node (ref "U10") (pin "8") (pinfunction "VCC_8") (pintype "power_in"))
    )
    (net (code "41") (name "Net-(J6A-D+)") (class "Default")
      (node (ref "J6") (pin "3A") (pinfunction "D+_3A") (pintype "bidirectional"))
      (node (ref "U12") (pin "3") (pinfunction "I/O2_3") (pintype "bidirectional"))
    )
    (net (code "42") (name "Net-(J6A-D-)") (class "Default")
      (node (ref "J6") (pin "2A") (pinfunction "D-_2A") (pintype "bidirectional"))
      (node (ref "U12") (pin "2") (pinfunction "I/O1_2") (pintype "bidirectional"))
    )
    (net (code "43") (name "Net-(J6A-VBUS)") (class "Default")
      (node (ref "F5") (pin "1") (pinfunction "1_1") (pintype "passive"))
      (node (ref "J6") (pin "1A") (pinfunction "VBUS_1A") (pintype "power_in"))
      (node (ref "U12") (pin "1") (pinfunction "VCC_1") (pintype "power_in"))
      (node (ref "U12") (pin "8") (pinfunction "VCC_8") (pintype "power_in"))
    )
    (net (code "44") (name "Net-(J6B-D+)") (class "Default")
      (node (ref "J6") (pin "3B") (pinfunction "D+_3B") (pintype "bidirectional"))
      (node (ref "U13") (pin "3") (pinfunction "I/O2_3") (pintype "bidirectional"))
    )
    (net (code "45") (name "Net-(J6B-D-)") (class "Default")
      (node (ref "J6") (pin "2B") (pinfunction "D-_2B") (pintype "bidirectional"))
      (node (ref "U13") (pin "2") (pinfunction "I/O1_2") (pintype "bidirectional"))
    )
    (net (code "46") (name "Net-(J6B-VBUS)") (class "Default")
      (node (ref "F6") (pin "1") (pinfunction "1_1") (pintype "passive"))
      (node (ref "J6") (pin "1B") (pinfunction "VBUS_1B") (pintype "power_in"))
      (node (ref "U13") (pin "1") (pinfunction "VCC_1") (pintype "power_in"))
      (node (ref "U13") (pin "8") (pinfunction "VCC_8") (pintype "power_in"))
    )
    (net (code "47") (name "Net-(L2-Pad1)") (class "Default")
      (node (ref "L2") (pin "1") (pinfunction "1_1") (pintype "passive"))
      (node (ref "U5") (pin "7") (pinfunction "I/O1_7") (pintype "bidirectional"))
    )
    (net (code "48") (name "Net-(L2-Pad2)") (class "Default")
      (node (ref "L2") (pin "2") (pinfunction "2_2") (pintype "passive"))
      (node (ref "U5") (pin "6") (pinfunction "I/O2_6") (pintype "bidirectional"))
    )
    (net (code "49") (name "Net-(L3-Pad1)") (class "Default")
      (node (ref "L3") (pin "1") (pinfunction "1_1") (pintype "passive"))
      (node (ref "U7") (pin "7") (pinfunction "I/O1_7") (pintype "bidirectional"))
    )
    (net (code "50") (name "Net-(L3-Pad2)") (class "Default")
      (node (ref "L3") (pin "2") (pinfunction "2_2") (pintype "passive"))
      (node (ref "U7") (pin "6") (pinfunction "I/O2_6") (pintype "bidirectional"))
    )
    (net (code "51") (name "Net-(L4-Pad1)") (class "Default")
      (node (ref "L4") (pin "1") (pinfunction "1_1") (pintype "passive"))
      (node (ref "U8") (pin "7") (pinfunction "I/O1_7") (pintype "bidirectional"))
    )
    (net (code "52") (name "Net-(L4-Pad2)") (class "Default")
      (node (ref "L4") (pin "2") (pinfunction "2_2") (pintype "passive"))
      (node (ref "U8") (pin "6") (pinfunction "I/O2_6") (pintype "bidirectional"))
    )
    (net (code "53") (name "Net-(L5-Pad1)") (class "Default")
      (node (ref "L5") (pin "1") (pinfunction "1_1") (pintype "passive"))
      (node (ref "U10") (pin "7") (pinfunction "I/O1_7") (pintype "bidirectional"))
    )
    (net (code "54") (name "Net-(L5-Pad2)") (class "Default")
      (node (ref "L5") (pin "2") (pinfunction "2_2") (pintype "passive"))
      (node (ref "U10") (pin "6") (pinfunction "I/O2_6") (pintype "bidirectional"))
    )
    (net (code "55") (name "Net-(L6-Pad1)") (class "Default")
      (node (ref "L6") (pin "1") (pinfunction "1_1") (pintype "passive"))
      (node (ref "U11") (pin "7") (pinfunction "I/O1_7") (pintype "bidirectional"))
    )
    (net (code "56") (name "Net-(L6-Pad2)") (class "Default")
      (node (ref "L6") (pin "2") (pinfunction "2_2") (pintype "passive"))
      (node (ref "U11") (pin "6") (pinfunction "I/O2_6") (pintype "bidirectional"))
    )
    (net (code "57") (name "Net-(L7-Pad1)") (class "Default")
      (node (ref "L7") (pin "1") (pinfunction "1_1") (pintype "passive"))
      (node (ref "U12") (pin "7") (pinfunction "I/O1_7") (pintype "bidirectional"))
    )
    (net (code "58") (name "Net-(L7-Pad2)") (class "Default")
      (node (ref "L7") (pin "2") (pinfunction "2_2") (pintype "passive"))
      (node (ref "U12") (pin "6") (pinfunction "I/O2_6") (pintype "bidirectional"))
    )
    (net (code "59") (name "Net-(L8-Pad1)") (class "Default")
      (node (ref "L8") (pin "1") (pinfunction "1_1") (pintype "passive"))
      (node (ref "U13") (pin "7") (pinfunction "I/O1_7") (pintype "bidirectional"))
    )
    (net (code "60") (name "Net-(L8-Pad2)") (class "Default")
      (node (ref "L8") (pin "2") (pinfunction "2_2") (pintype "passive"))
      (node (ref "U13") (pin "6") (pinfunction "I/O2_6") (pintype "bidirectional"))
    )
    (net (code "61") (name "Net-(LED1-Anode)") (class "Default")
      (node (ref "LED1") (pin "2") (pinfunction "Anode_2") (pintype "passive"))
      (node (ref "R23") (pin "1") (pinfunction "1_1") (pintype "passive"))
    )
    (net (code "62") (name "Net-(LED1-Cathode)") (class "Default")
      (node (ref "LED1") (pin "1") (pinfunction "Cathode_1") (pintype "passive"))
      (node (ref "U9") (pin "51") (pinfunction "LED_A1_N/PRT_SWP1_51") (pintype "bidirectional"))
    )
    (net (code "63") (name "Net-(LED2-Anode)") (class "Default")
      (node (ref "LED2") (pin "2") (pinfunction "Anode_2") (pintype "passive"))
      (node (ref "R24") (pin "1") (pinfunction "1_1") (pintype "passive"))
    )
    (net (code "64") (name "Net-(LED2-Cathode)") (class "Default")
      (node (ref "LED2") (pin "1") (pinfunction "Cathode_1") (pintype "passive"))
      (node (ref "U9") (pin "49") (pinfunction "LED_A2_N/PRT_SWP2_49") (pintype "bidirectional"))
    )
    (net (code "65") (name "Net-(LED3-Anode)") (class "Default")
      (node (ref "LED3") (pin "2") (pinfunction "Anode_2") (pintype "passive"))
      (node (ref "R27") (pin "1") (pinfunction "1_1") (pintype "passive"))
    )
    (net (code "66") (name "Net-(LED3-Cathode)") (class "Default")
      (node (ref "LED3") (pin "1") (pinfunction "Cathode_1") (pintype "passive"))
      (node (ref "U9") (pin "47") (pinfunction "LED_A3_N/PRT_SWP3_47") (pintype "bidirectional"))
    )
    (net (code "67") (name "Net-(LED4-Anode)") (class "Default")
      (node (ref "LED4") (pin "2") (pinfunction "Anode_2") (pintype "passive"))
      (node (ref "R29") (pin "1") (pinfunction "1_1") (pintype "passive"))
    )
    (net (code "68") (name "Net-(LED4-Cathode)") (class "Default")
      (node (ref "LED4") (pin "1") (pinfunction "Cathode_1") (pintype "passive"))
      (node (ref "U9") (pin "33") (pinfunction "LED_A4_N/PRT_SWP4_33") (pintype "bidirectional"))
    )
    (net (code "69") (name "Net-(LED5-Anode)") (class "Default")
      (node (ref "LED5") (pin "2") (pinfunction "Anode_2") (pintype "passive"))
      (node (ref "R33") (pin "1") (pinfunction "1_1") (pintype "passive"))
    )
    (net (code "70") (name "Net-(LED6-Anode)") (class "Default")
      (node (ref "LED6") (pin "2") (pinfunction "Anode_2") (pintype "passive"))
      (node (ref "R34") (pin "1") (pinfunction "1_1") (pintype "passive"))
    )
    (net (code "71") (name "Net-(LED6-Cathode)") (class "Default")
      (node (ref "LED6") (pin "1") (pinfunction "Cathode_1") (pintype "passive"))
      (node (ref "U9") (pin "31") (pinfunction "LED_A5_N/PRT_SWP5_31") (pintype "bidirectional"))
    )
    (net (code "72") (name "Net-(LED7-Anode)") (class "Default")
      (node (ref "LED7") (pin "2") (pinfunction "Anode_2") (pintype "passive"))
      (node (ref "R38") (pin "1") (pinfunction "1_1") (pintype "passive"))
    )
    (net (code "73") (name "Net-(LED7-Cathode)") (class "Default")
      (node (ref "LED7") (pin "1") (pinfunction "Cathode_1") (pintype "passive"))
      (node (ref "U9") (pin "17") (pinfunction "LED_A6_N/PRT_SWP6_17") (pintype "bidirectional"))
    )
    (net (code "74") (name "Net-(LED8-Anode)") (class "Default")
      (node (ref "LED8") (pin "2") (pinfunction "Anode_2") (pintype "passive"))
      (node (ref "R41") (pin "1") (pinfunction "1_1") (pintype "passive"))
    )
    (net (code "75") (name "Net-(LED8-Cathode)") (class "Default")
      (node (ref "LED8") (pin "1") (pinfunction "Cathode_1") (pintype "passive"))
      (node (ref "U9") (pin "15") (pinfunction "LED_A7_N/PRT_SWP7_15") (pintype "bidirectional"))
    )
    (net (code "76") (name "Net-(U9-CFG_SEL2)") (class "Default")
      (node (ref "R35") (pin "2") (pinfunction "2_2") (pintype "passive"))
      (node (ref "U9") (pin "13") (pinfunction "CFG_SEL2_13") (pintype "bidirectional"))
    )
    (net (code "77") (name "Net-(U9-HS_IND{slash}CFG_SEL1)") (class "Default")
      (node (ref "R32") (pin "2") (pinfunction "2_2") (pintype "passive"))
      (node (ref "R33") (pin "2") (pinfunction "2_2") (pintype "passive"))
      (node (ref "U9") (pin "42") (pinfunction "HS_IND/CFG_SEL1_42") (pintype "bidirectional"))
    )
    (net (code "78") (name "Net-(U9-RBIAS)") (class "Default")
      (node (ref "R36") (pin "2") (pinfunction "2_2") (pintype "passive"))
      (node (ref "U9") (pin "63") (pinfunction "RBIAS_63") (pintype "bidirectional"))
    )
    (net (code "79") (name "Net-(U9-RESET_N)") (class "Default")
      (node (ref "C40") (pin "1") (pinfunction "1_1") (pintype "passive"))
      (node (ref "R39") (pin "2") (pinfunction "2_2") (pintype "passive"))
      (node (ref "U9") (pin "43") (pinfunction "RESET_N_43") (pintype "bidirectional"))
    )
    (net (code "80") (name "Net-(U9-SCL{slash}SMBCLK{slash}CFG_SEL0)") (class "Default")
      (node (ref "R31") (pin "2") (pinfunction "2_2") (pintype "passive"))
      (node (ref "U9") (pin "41") (pinfunction "SCL/SMBCLK/CFG_SEL0_41") (pintype "bidirectional"))
    )
    (net (code "81") (name "Net-(U9-SDA{slash}SMBDATA{slash}NON_REM1)") (class "Default")
      (node (ref "R30") (pin "2") (pinfunction "2_2") (pintype "passive"))
      (node (ref "U9") (pin "40") (pinfunction "SDA/SMBDATA/NON_REM1_40") (pintype "bidirectional"))
    )
    (net (code "82") (name "Net-(U9-SUSP_IND{slash}LOCAL_PWR)") (class "Default")
      (node (ref "R40") (pin "2") (pinfunction "2_2") (pintype "passive"))
      (node (ref "U9") (pin "45") (pinfunction "SUSP_IND/LOCAL_PWR_45") (pintype "bidirectional"))
    )
    (net (code "83") (name "Net-(U9-TEST)") (class "Default")
      (node (ref "R37") (pin "2") (pinfunction "2_2") (pintype "passive"))
      (node (ref "U9") (pin "19") (pinfunction "TEST_19") (pintype "bidirectional"))
    )
    (net (code "84") (name "Net-(U9-VBUS_DET)") (class "Default")
      (node (ref "R25") (pin "2") (pinfunction "2_2") (pintype "passive"))
      (node (ref "R26") (pin "2") (pinfunction "2_2") (pintype "passive"))
      (node (ref "U9") (pin "44") (pinfunction "VBUS_DET_44") (pintype "bidirectional"))
    )
    (net (code "85") (name "Net-(U9-VDD18)") (class "Default")
      (node (ref "C29") (pin "1") (pinfunction "1_1") (pintype "passive"))
      (node (ref "C30") (pin "1") (pinfunction "1_1") (pintype "passive"))
      (node (ref "U9") (pin "25") (pinfunction "VDD18_25") (pintype "power_in"))
    )
    (net (code "86") (name "Net-(U9-VDD18PLL)") (class "Default")
      (node (ref "C27") (pin "1") (pinfunction "1_1") (pintype "passive"))
      (node (ref "C28") (pin "1") (pinfunction "1_1") (pintype "passive"))
      (node (ref "U9") (pin "62") (pinfunction "VDD18PLL_62") (pintype "power_in"))
    )
    (net (code "87") (name "Net-(U9-XTAL1{slash}CLKIN)") (class "Default")
      (node (ref "C38") (pin "1") (pinfunction "1_1") (pintype "passive"))
      (node (ref "R28") (pin "1") (pinfunction "1_1") (pintype "passive"))
      (node (ref "U9") (pin "61") (pinfunction "XTAL1/CLKIN_61") (pintype "bidirectional"))
      (node (ref "Y2") (pin "1") (pintype "passive"))
    )
    (net (code "88") (name "Net-(U9-XTAL2)") (class "Default")
      (node (ref "C39") (pin "1") (pinfunction "1_1") (pintype "passive"))
      (node (ref "R28") (pin "2") (pinfunction "2_2") (pintype "passive"))
      (node (ref "U9") (pin "60") (pinfunction "XTAL2_60") (pintype "bidirectional"))
      (node (ref "Y2") (pin "3") (pintype "passive"))
    )
    (net (code "89") (name "OTG_VB") (class "Default")
      (node (ref "J4") (pin "1") (pinfunction "VCC_1") (pintype "power_in"))
      (node (ref "R22") (pin "1") (pinfunction "1_1") (pintype "passive"))
      (node (ref "U5") (pin "1") (pinfunction "VCC_1") (pintype "power_in"))
      (node (ref "U5") (pin "8") (pinfunction "VCC_8") (pintype "power_in"))
    )
    (net (code "90") (name "USB2_UP_N") (class "Default")
      (node (ref "U6") (pin "4") (pinfunction "D-_4") (pintype "bidirectional"))
    )
    (net (code "91") (name "USB2_UP_OTG") (class "Default")
      (node (ref "R21") (pin "2") (pinfunction "2_2") (pintype "passive"))
      (node (ref "R22") (pin "2") (pinfunction "2_2") (pintype "passive"))
      (node (ref "U6") (pin "2") (pinfunction "SEL_2") (pintype "input"))
    )
    (net (code "92") (name "USB2_UP_P") (class "Default")
      (node (ref "U6") (pin "3") (pinfunction "D+_3") (pintype "bidirectional"))
    )
    (net (code "93") (name "unconnected-(FUSB1-Pad9)") (class "Default")
      (node (ref "FUSB1") (pin "9") (pinfunction "9_9") (pintype "passive"))
    )
    (net (code "94") (name "unconnected-(FUSB1-Pad10)") (class "Default")
      (node (ref "FUSB1") (pin "10") (pinfunction "10_10") (pintype "passive"))
    )
    (net (code "95") (name "unconnected-(J4-ID-Pad4)") (class "Default")
      (node (ref "J4") (pin "4") (pinfunction "ID_4") (pintype "bidirectional"))
    )
    (net (code "96") (name "unconnected-(U9-LED_B1_N{slash}BOOST0-Pad50)") (class "Default")
      (node (ref "U9") (pin "50") (pinfunction "LED_B1_N/BOOST0_50") (pintype "bidirectional"))
    )
    (net (code "97") (name "unconnected-(U9-LED_B2_N{slash}BOOST1-Pad48)") (class "Default")
      (node (ref "U9") (pin "48") (pinfunction "LED_B2_N/BOOST1_48") (pintype "bidirectional"))
    )
    (net (code "98") (name "unconnected-(U9-LED_B3_N{slash}GANG_EN-Pad34)") (class "Default")
      (node (ref "U9") (pin "34") (pinfunction "LED_B3_N/GANG_EN_34") (pintype "bidirectional"))
    )
    (net (code "99") (name "unconnected-(U9-LED_B4_N-Pad32)") (class "Default")
      (node (ref "U9") (pin "32") (pinfunction "LED_B4_N_32") (pintype "bidirectional"))
    )
    (net (code "100") (name "unconnected-(U9-LED_B5_N-Pad18)") (class "Default")
      (node (ref "U9") (pin "18") (pinfunction "LED_B5_N_18") (pintype "bidirectional"))
    )
    (net (code "101") (name "unconnected-(U9-LED_B6_N-Pad16)") (class "Default")
      (node (ref "U9") (pin "16") (pinfunction "LED_B6_N_16") (pintype "bidirectional"))
    )
    (net (code "102") (name "unconnected-(U9-LED_B7_N-Pad14)") (class "Default")
      (node (ref "U9") (pin "14") (pinfunction "LED_B7_N_14") (pintype "bidirectional"))
    )
    (net (code "103") (name "unconnected-(U9-OCS1_N-Pad28)") (class "Default")
      (node (ref "U9") (pin "28") (pinfunction "OCS1_N_28") (pintype "bidirectional"))
    )
    (net (code "104") (name "unconnected-(U9-OCS2_N-Pad27)") (class "Default")
      (node (ref "U9") (pin "27") (pinfunction "OCS2_N_27") (pintype "bidirectional"))
    )
    (net (code "105") (name "unconnected-(U9-OCS3_N-Pad22)") (class "Default")
      (node (ref "U9") (pin "22") (pinfunction "OCS3_N_22") (pintype "bidirectional"))
    )
    (net (code "106") (name "unconnected-(U9-OCS4_N-Pad21)") (class "Default")
      (node (ref "U9") (pin "21") (pinfunction "OCS4_N_21") (pintype "bidirectional"))
    )
    (net (code "107") (name "unconnected-(U9-OCS5_N-Pad35)") (class "Default")
      (node (ref "U9") (pin "35") (pinfunction "OCS5_N_35") (pintype "bidirectional"))
    )
    (net (code "108") (name "unconnected-(U9-OCS6_N-Pad38)") (class "Default")
      (node (ref "U9") (pin "38") (pinfunction "OCS6_N_38") (pintype "bidirectional"))
    )
    (net (code "109") (name "unconnected-(U9-OCS7_N-Pad37)") (class "Default")
      (node (ref "U9") (pin "37") (pinfunction "OCS7_N_37") (pintype "bidirectional"))
    )
    (net (code "110") (name "unconnected-(U9-PRTPWR1-Pad29)") (class "Default")
      (node (ref "U9") (pin "29") (pinfunction "PRTPWR1_29") (pintype "bidirectional"))
    )
    (net (code "111") (name "unconnected-(U9-PRTPWR2-Pad26)") (class "Default")
      (node (ref "U9") (pin "26") (pinfunction "PRTPWR2_26") (pintype "bidirectional"))
    )
    (net (code "112") (name "unconnected-(U9-PRTPWR3-Pad23)") (class "Default")
      (node (ref "U9") (pin "23") (pinfunction "PRTPWR3_23") (pintype "bidirectional"))
    )
    (net (code "113") (name "unconnected-(U9-PRTPWR4-Pad20)") (class "Default")
      (node (ref "U9") (pin "20") (pinfunction "PRTPWR4_20") (pintype "bidirectional"))
    )
    (net (code "114") (name "unconnected-(U9-PRTPWR5-Pad30)") (class "Default")
      (node (ref "U9") (pin "30") (pinfunction "PRTPWR5_30") (pintype "bidirectional"))
    )
    (net (code "115") (name "unconnected-(U9-PRTPWR6-Pad39)") (class "Default")
      (node (ref "U9") (pin "39") (pinfunction "PRTPWR6_39") (pintype "bidirectional"))
    )
    (net (code "116") (name "unconnected-(U9-PRTPWR7-Pad36)") (class "Default")
      (node (ref "U9") (pin "36") (pinfunction "PRTPWR7_36") (pintype "bidirectional"))
    )
  )
)
